# Sheet1.net
KiCad netlist of a schematic drawn in Altium Designer
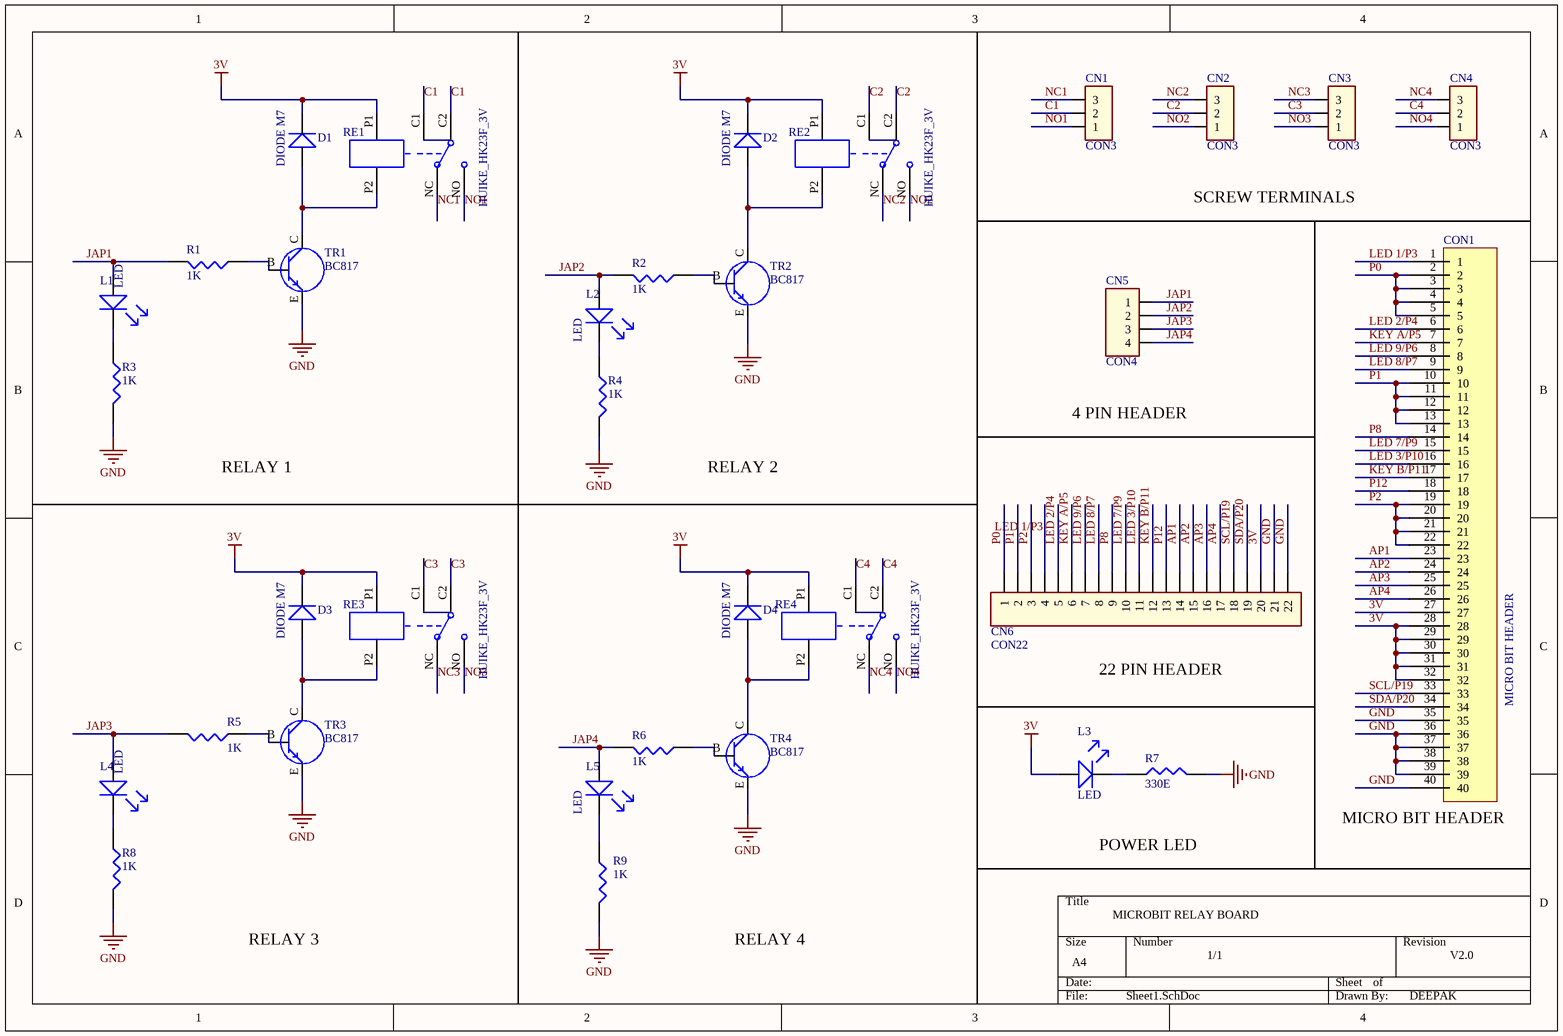
[diagram p0: Sheet1.SchDoc]

(export (version "E")
  (design (tool "Eeschema 10.0.6"))
  (components
    (comp (ref "CN1") (value "CON3") (footprint "CON3_3.5") (libsource (lib "dxp_pasl_lib") (part "CON3")))
    (comp (ref "CN2") (value "CON3") (footprint "CON3_3.5") (libsource (lib "dxp_pasl_lib") (part "CON3")))
    (comp (ref "CN3") (value "CON3") (footprint "CON3_3.5") (libsource (lib "dxp_pasl_lib") (part "CON3")))
    (comp (ref "CN4") (value "CON3") (footprint "CON3_3.5") (libsource (lib "dxp_pasl_lib") (part "CON3")))
    (comp (ref "CN5") (value "CON4") (footprint "CON4_BJ") (libsource (lib "dxp_pasl_lib") (part "CON4")))
    (comp (ref "CN6")
      (value "CON22")
      (footprint "CON22  berg")
      (libsource (lib "dxp_pasl_lib") (part "CON22"))
    )
    (comp (ref "CON1")
      (value "MICRO BIT HEADER")
      (footprint "MICROBIT HEADER STRAIGHT")
      (libsource (lib "dxp_pasl_lib") (part "MICRO BIT HEADER 40 PIN"))
    )
    (comp (ref "D1")
      (value "DIODE M7")
      (footprint "M7 SMO_DO-214AC")
      (libsource (lib "dxp_pasl_lib") (part "DIODE"))
    )
    (comp (ref "D2")
      (value "DIODE M7")
      (footprint "M7 SMO_DO-214AC")
      (libsource (lib "dxp_pasl_lib") (part "DIODE"))
    )
    (comp (ref "D3")
      (value "DIODE M7")
      (footprint "M7 SMO_DO-214AC")
      (libsource (lib "dxp_pasl_lib") (part "DIODE"))
    )
    (comp (ref "D4")
      (value "DIODE M7")
      (footprint "M7 SMO_DO-214AC")
      (libsource (lib "dxp_pasl_lib") (part "DIODE"))
    )
    (comp (ref "L1") (value "LED") (footprint "0805 _LED") (libsource (lib "dxp_pasl_lib") (part "LED")))
    (comp (ref "L2") (value "LED") (footprint "0805 _LED") (libsource (lib "dxp_pasl_lib") (part "LED")))
    (comp (ref "L3") (value "LED") (footprint "0805 _LED") (libsource (lib "dxp_pasl_lib") (part "LED")))
    (comp (ref "L4") (value "LED") (footprint "0805 _LED") (libsource (lib "dxp_pasl_lib") (part "LED")))
    (comp (ref "L5") (value "LED") (footprint "0805 _LED") (libsource (lib "dxp_pasl_lib") (part "LED")))
    (comp (ref "R1") (value "1K") (footprint "0603") (libsource (lib "dxp_pasl_lib") (part "RES")))
    (comp (ref "R2") (value "1K") (footprint "0603") (libsource (lib "dxp_pasl_lib") (part "RES")))
    (comp (ref "R3") (value "1K") (footprint "0603") (libsource (lib "dxp_pasl_lib") (part "RES")))
    (comp (ref "R4") (value "1K") (footprint "0603") (libsource (lib "dxp_pasl_lib") (part "RES")))
    (comp (ref "R5") (value "1K") (footprint "0603") (libsource (lib "dxp_pasl_lib") (part "RES")))
    (comp (ref "R6") (value "1K") (footprint "0603") (libsource (lib "dxp_pasl_lib") (part "RES")))
    (comp (ref "R7") (value "330E") (footprint "0603") (libsource (lib "dxp_pasl_lib") (part "RES")))
    (comp (ref "R8") (value "1K") (footprint "0603") (libsource (lib "dxp_pasl_lib") (part "RES")))
    (comp (ref "R9") (value "1K") (footprint "0603") (libsource (lib "dxp_pasl_lib") (part "RES")))
    (comp (ref "RE1")
      (value "HUIKE_HK23F_3V")
      (footprint "HK23F_RELAY")
      (libsource (lib "dxp_pasl_lib") (part "HUIKE_HK23F_3V"))
    )
    (comp (ref "RE2")
      (value "HUIKE_HK23F_3V")
      (footprint "HK23F_RELAY")
      (libsource (lib "dxp_pasl_lib") (part "HUIKE_HK23F_3V"))
    )
    (comp (ref "RE3")
      (value "HUIKE_HK23F_3V")
      (footprint "HK23F_RELAY")
      (libsource (lib "dxp_pasl_lib") (part "HUIKE_HK23F_3V"))
    )
    (comp (ref "RE4")
      (value "HUIKE_HK23F_3V")
      (footprint "HK23F_RELAY")
      (libsource (lib "dxp_pasl_lib") (part "HUIKE_HK23F_3V"))
    )
    (comp (ref "TR1")
      (value "BC817")
      (footprint "547_SOT23")
      (libsource (lib "dxp_pasl_lib") (part "TRANSISTER_NPN"))
    )
    (comp (ref "TR2")
      (value "BC817")
      (footprint "547_SOT23")
      (libsource (lib "dxp_pasl_lib") (part "TRANSISTER_NPN"))
    )
    (comp (ref "TR3")
      (value "BC817")
      (footprint "547_SOT23")
      (libsource (lib "dxp_pasl_lib") (part "TRANSISTER_NPN"))
    )
    (comp (ref "TR4")
      (value "BC817")
      (footprint "547_SOT23")
      (libsource (lib "dxp_pasl_lib") (part "TRANSISTER_NPN"))
    )
  )
  (nets
    (net (code "1") (name "/AP1") (class "Default")
      (node (ref "CN6") (pin "14") (pinfunction "14_14") (pintype "passive"))
      (node (ref "CON1") (pin "23") (pinfunction "23_23") (pintype "passive"))
    )
    (net (code "2") (name "/AP2") (class "Default")
      (node (ref "CN6") (pin "15") (pinfunction "15_15") (pintype "passive"))
      (node (ref "CON1") (pin "24") (pinfunction "24_24") (pintype "passive"))
    )
    (net (code "3") (name "/AP3") (class "Default")
      (node (ref "CN6") (pin "16") (pinfunction "16_16") (pintype "passive"))
      (node (ref "CON1") (pin "25") (pinfunction "25_25") (pintype "passive"))
    )
    (net (code "4") (name "/AP4") (class "Default")
      (node (ref "CN6") (pin "17") (pinfunction "17_17") (pintype "passive"))
      (node (ref "CON1") (pin "26") (pinfunction "26_26") (pintype "passive"))
    )
    (net (code "5") (name "/C1") (class "Default")
      (node (ref "CN1") (pin "2") (pinfunction "2_2") (pintype "passive"))
      (node (ref "RE1") (pin "C1") (pinfunction "C1_C1") (pintype "passive"))
      (node (ref "RE1") (pin "C2") (pinfunction "C2_C2") (pintype "passive"))
    )
    (net (code "6") (name "/C2") (class "Default")
      (node (ref "CN2") (pin "2") (pinfunction "2_2") (pintype "passive"))
      (node (ref "RE2") (pin "C1") (pinfunction "C1_C1") (pintype "passive"))
      (node (ref "RE2") (pin "C2") (pinfunction "C2_C2") (pintype "passive"))
    )
    (net (code "7") (name "/C3") (class "Default")
      (node (ref "CN3") (pin "2") (pinfunction "2_2") (pintype "passive"))
      (node (ref "RE3") (pin "C1") (pinfunction "C1_C1") (pintype "passive"))
      (node (ref "RE3") (pin "C2") (pinfunction "C2_C2") (pintype "passive"))
    )
    (net (code "8") (name "/C4") (class "Default")
      (node (ref "CN4") (pin "2") (pinfunction "2_2") (pintype "passive"))
      (node (ref "RE4") (pin "C1") (pinfunction "C1_C1") (pintype "passive"))
      (node (ref "RE4") (pin "C2") (pinfunction "C2_C2") (pintype "passive"))
    )
    (net (code "9") (name "/JAP1") (class "Default")
      (node (ref "CN5") (pin "1") (pinfunction "1_1") (pintype "passive"))
      (node (ref "L1") (pin "A") (pinfunction "A_A") (pintype "passive"))
      (node (ref "R1") (pin "2") (pinfunction "2_2") (pintype "passive"))
    )
    (net (code "10") (name "/JAP2") (class "Default")
      (node (ref "CN5") (pin "2") (pinfunction "2_2") (pintype "passive"))
      (node (ref "L2") (pin "A") (pinfunction "A_A") (pintype "passive"))
      (node (ref "R2") (pin "2") (pinfunction "2_2") (pintype "passive"))
    )
    (net (code "11") (name "/JAP3") (class "Default")
      (node (ref "CN5") (pin "3") (pinfunction "3_3") (pintype "passive"))
      (node (ref "L4") (pin "A") (pinfunction "A_A") (pintype "passive"))
      (node (ref "R5") (pin "2") (pinfunction "2_2") (pintype "passive"))
    )
    (net (code "12") (name "/JAP4") (class "Default")
      (node (ref "CN5") (pin "4") (pinfunction "4_4") (pintype "passive"))
      (node (ref "L5") (pin "A") (pinfunction "A_A") (pintype "passive"))
      (node (ref "R6") (pin "2") (pinfunction "2_2") (pintype "passive"))
    )
    (net (code "13") (name "/KEY A{slash}P5") (class "Default")
      (node (ref "CN6") (pin "6") (pinfunction "6_6") (pintype "passive"))
      (node (ref "CON1") (pin "7") (pinfunction "7_7") (pintype "passive"))
    )
    (net (code "14") (name "/KEY B{slash}P11") (class "Default")
      (node (ref "CN6") (pin "12") (pinfunction "12_12") (pintype "passive"))
      (node (ref "CON1") (pin "17") (pinfunction "17_17") (pintype "passive"))
    )
    (net (code "15") (name "/LED 1{slash}P3") (class "Default")
      (node (ref "CN6") (pin "4") (pinfunction "4_4") (pintype "passive"))
      (node (ref "CON1") (pin "1") (pinfunction "1_1") (pintype "passive"))
    )
    (net (code "16") (name "/LED 2{slash}P4") (class "Default")
      (node (ref "CN6") (pin "5") (pinfunction "5_5") (pintype "passive"))
      (node (ref "CON1") (pin "6") (pinfunction "6_6") (pintype "passive"))
    )
    (net (code "17") (name "/LED 3{slash}P10") (class "Default")
      (node (ref "CN6") (pin "11") (pinfunction "11_11") (pintype "passive"))
      (node (ref "CON1") (pin "16") (pinfunction "16_16") (pintype "passive"))
    )
    (net (code "18") (name "/LED 7{slash}P9") (class "Default")
      (node (ref "CN6") (pin "10") (pinfunction "10_10") (pintype "passive"))
      (node (ref "CON1") (pin "15") (pinfunction "15_15") (pintype "passive"))
    )
    (net (code "19") (name "/LED 8{slash}P7") (class "Default")
      (node (ref "CN6") (pin "8") (pinfunction "8_8") (pintype "passive"))
      (node (ref "CON1") (pin "9") (pinfunction "9_9") (pintype "passive"))
    )
    (net (code "20") (name "/LED 9{slash}P6") (class "Default")
      (node (ref "CN6") (pin "7") (pinfunction "7_7") (pintype "passive"))
      (node (ref "CON1") (pin "8") (pinfunction "8_8") (pintype "passive"))
    )
    (net (code "21") (name "/NC1") (class "Default")
      (node (ref "CN1") (pin "3") (pinfunction "3_3") (pintype "passive"))
      (node (ref "RE1") (pin "NC") (pinfunction "NC_NC") (pintype "passive"))
    )
    (net (code "22") (name "/NC2") (class "Default")
      (node (ref "CN2") (pin "3") (pinfunction "3_3") (pintype "passive"))
      (node (ref "RE2") (pin "NC") (pinfunction "NC_NC") (pintype "passive"))
    )
    (net (code "23") (name "/NC3") (class "Default")
      (node (ref "CN3") (pin "3") (pinfunction "3_3") (pintype "passive"))
      (node (ref "RE3") (pin "NC") (pinfunction "NC_NC") (pintype "passive"))
    )
    (net (code "24") (name "/NC4") (class "Default")
      (node (ref "CN4") (pin "3") (pinfunction "3_3") (pintype "passive"))
      (node (ref "RE4") (pin "NC") (pinfunction "NC_NC") (pintype "passive"))
    )
    (net (code "25") (name "/NO1") (class "Default")
      (node (ref "CN1") (pin "1") (pinfunction "1_1") (pintype "passive"))
      (node (ref "RE1") (pin "NO") (pinfunction "NO_NO") (pintype "passive"))
    )
    (net (code "26") (name "/NO2") (class "Default")
      (node (ref "CN2") (pin "1") (pinfunction "1_1") (pintype "passive"))
      (node (ref "RE2") (pin "NO") (pinfunction "NO_NO") (pintype "passive"))
    )
    (net (code "27") (name "/NO3") (class "Default")
      (node (ref "CN3") (pin "1") (pinfunction "1_1") (pintype "passive"))
      (node (ref "RE3") (pin "NO") (pinfunction "NO_NO") (pintype "passive"))
    )
    (net (code "28") (name "/NO4") (class "Default")
      (node (ref "CN4") (pin "1") (pinfunction "1_1") (pintype "passive"))
      (node (ref "RE4") (pin "NO") (pinfunction "NO_NO") (pintype "passive"))
    )
    (net (code "29") (name "/P0") (class "Default")
      (node (ref "CN6") (pin "1") (pinfunction "1_1") (pintype "passive"))
      (node (ref "CON1") (pin "2") (pinfunction "2_2") (pintype "passive"))
      (node (ref "CON1") (pin "3") (pinfunction "3_3") (pintype "passive"))
      (node (ref "CON1") (pin "4") (pinfunction "4_4") (pintype "passive"))
      (node (ref "CON1") (pin "5") (pinfunction "5_5") (pintype "passive"))
    )
    (net (code "30") (name "/P1") (class "Default")
      (node (ref "CN6") (pin "2") (pinfunction "2_2") (pintype "passive"))
      (node (ref "CON1") (pin "10") (pinfunction "10_10") (pintype "passive"))
      (node (ref "CON1") (pin "11") (pinfunction "11_11") (pintype "passive"))
      (node (ref "CON1") (pin "12") (pinfunction "12_12") (pintype "passive"))
      (node (ref "CON1") (pin "13") (pinfunction "13_13") (pintype "passive"))
    )
    (net (code "31") (name "/P2") (class "Default")
      (node (ref "CN6") (pin "3") (pinfunction "3_3") (pintype "passive"))
      (node (ref "CON1") (pin "19") (pinfunction "19_19") (pintype "passive"))
      (node (ref "CON1") (pin "20") (pinfunction "20_20") (pintype "passive"))
      (node (ref "CON1") (pin "21") (pinfunction "21_21") (pintype "passive"))
      (node (ref "CON1") (pin "22") (pinfunction "22_22") (pintype "passive"))
    )
    (net (code "32") (name "/P8") (class "Default")
      (node (ref "CN6") (pin "9") (pinfunction "9_9") (pintype "passive"))
      (node (ref "CON1") (pin "14") (pinfunction "14_14") (pintype "passive"))
    )
    (net (code "33") (name "/P12") (class "Default")
      (node (ref "CN6") (pin "13") (pinfunction "13_13") (pintype "passive"))
      (node (ref "CON1") (pin "18") (pinfunction "18_18") (pintype "passive"))
    )
    (net (code "34") (name "/SCL{slash}P19") (class "Default")
      (node (ref "CN6") (pin "18") (pinfunction "18_18") (pintype "passive"))
      (node (ref "CON1") (pin "33") (pinfunction "33_33") (pintype "passive"))
    )
    (net (code "35") (name "/SDA{slash}P20") (class "Default")
      (node (ref "CN6") (pin "19") (pinfunction "19_19") (pintype "passive"))
      (node (ref "CON1") (pin "34") (pinfunction "34_34") (pintype "passive"))
    )
    (net (code "36") (name "3V") (class "Default")
      (node (ref "CN6") (pin "20") (pinfunction "20_20") (pintype "passive"))
      (node (ref "CON1") (pin "27") (pinfunction "27_27") (pintype "passive"))
      (node (ref "CON1") (pin "28") (pinfunction "28_28") (pintype "passive"))
      (node (ref "CON1") (pin "29") (pinfunction "29_29") (pintype "passive"))
      (node (ref "CON1") (pin "30") (pinfunction "30_30") (pintype "passive"))
      (node (ref "CON1") (pin "31") (pinfunction "31_31") (pintype "passive"))
      (node (ref "CON1") (pin "32") (pinfunction "32_32") (pintype "passive"))
      (node (ref "D1") (pin "K") (pinfunction "K_K") (pintype "passive"))
      (node (ref "D2") (pin "K") (pinfunction "K_K") (pintype "passive"))
      (node (ref "D3") (pin "K") (pinfunction "K_K") (pintype "passive"))
      (node (ref "D4") (pin "K") (pinfunction "K_K") (pintype "passive"))
      (node (ref "L3") (pin "A") (pinfunction "A_A") (pintype "passive"))
      (node (ref "RE1") (pin "P1") (pinfunction "P1_P1") (pintype "passive"))
      (node (ref "RE2") (pin "P1") (pinfunction "P1_P1") (pintype "passive"))
      (node (ref "RE3") (pin "P1") (pinfunction "P1_P1") (pintype "passive"))
      (node (ref "RE4") (pin "P1") (pinfunction "P1_P1") (pintype "passive"))
    )
    (net (code "37") (name "GND") (class "Default")
      (node (ref "CN6") (pin "21") (pinfunction "21_21") (pintype "passive"))
      (node (ref "CN6") (pin "22") (pinfunction "22_22") (pintype "passive"))
      (node (ref "CON1") (pin "35") (pinfunction "35_35") (pintype "passive"))
      (node (ref "CON1") (pin "36") (pinfunction "36_36") (pintype "passive"))
      (node (ref "CON1") (pin "37") (pinfunction "37_37") (pintype "passive"))
      (node (ref "CON1") (pin "38") (pinfunction "38_38") (pintype "passive"))
      (node (ref "CON1") (pin "39") (pinfunction "39_39") (pintype "passive"))
      (node (ref "CON1") (pin "40") (pinfunction "40_40") (pintype "passive"))
      (node (ref "R3") (pin "2") (pinfunction "2_2") (pintype "passive"))
      (node (ref "R4") (pin "2") (pinfunction "2_2") (pintype "passive"))
      (node (ref "R7") (pin "2") (pinfunction "2_2") (pintype "passive"))
      (node (ref "R8") (pin "2") (pinfunction "2_2") (pintype "passive"))
      (node (ref "R9") (pin "2") (pinfunction "2_2") (pintype "passive"))
      (node (ref "TR1") (pin "E") (pinfunction "E_E") (pintype "passive"))
      (node (ref "TR2") (pin "E") (pinfunction "E_E") (pintype "passive"))
      (node (ref "TR3") (pin "E") (pinfunction "E_E") (pintype "passive"))
      (node (ref "TR4") (pin "E") (pinfunction "E_E") (pintype "passive"))
    )
    (net (code "38") (name "Net-(D1-PadA)") (class "Default")
      (node (ref "D1") (pin "A") (pinfunction "A_A") (pintype "passive"))
      (node (ref "RE1") (pin "P2") (pinfunction "P2_P2") (pintype "passive"))
      (node (ref "TR1") (pin "C") (pinfunction "C_C") (pintype "passive"))
    )
    (net (code "39") (name "Net-(D2-PadA)") (class "Default")
      (node (ref "D2") (pin "A") (pinfunction "A_A") (pintype "passive"))
      (node (ref "RE2") (pin "P2") (pinfunction "P2_P2") (pintype "passive"))
      (node (ref "TR2") (pin "C") (pinfunction "C_C") (pintype "passive"))
    )
    (net (code "40") (name "Net-(D3-PadA)") (class "Default")
      (node (ref "D3") (pin "A") (pinfunction "A_A") (pintype "passive"))
      (node (ref "RE3") (pin "P2") (pinfunction "P2_P2") (pintype "passive"))
      (node (ref "TR3") (pin "C") (pinfunction "C_C") (pintype "passive"))
    )
    (net (code "41") (name "Net-(D4-PadA)") (class "Default")
      (node (ref "D4") (pin "A") (pinfunction "A_A") (pintype "passive"))
      (node (ref "RE4") (pin "P2") (pinfunction "P2_P2") (pintype "passive"))
      (node (ref "TR4") (pin "C") (pinfunction "C_C") (pintype "passive"))
    )
    (net (code "42") (name "Net-(L1-PadK)") (class "Default")
      (node (ref "L1") (pin "K") (pinfunction "K_K") (pintype "passive"))
      (node (ref "R3") (pin "1") (pinfunction "1_1") (pintype "passive"))
    )
    (net (code "43") (name "Net-(L2-PadK)") (class "Default")
      (node (ref "L2") (pin "K") (pinfunction "K_K") (pintype "passive"))
      (node (ref "R4") (pin "1") (pinfunction "1_1") (pintype "passive"))
    )
    (net (code "44") (name "Net-(L3-PadK)") (class "Default")
      (node (ref "L3") (pin "K") (pinfunction "K_K") (pintype "passive"))
      (node (ref "R7") (pin "1") (pinfunction "1_1") (pintype "passive"))
    )
    (net (code "45") (name "Net-(L4-PadK)") (class "Default")
      (node (ref "L4") (pin "K") (pinfunction "K_K") (pintype "passive"))
      (node (ref "R8") (pin "1") (pinfunction "1_1") (pintype "passive"))
    )
    (net (code "46") (name "Net-(L5-PadK)") (class "Default")
      (node (ref "L5") (pin "K") (pinfunction "K_K") (pintype "passive"))
      (node (ref "R9") (pin "1") (pinfunction "1_1") (pintype "passive"))
    )
    (net (code "47") (name "Net-(R1-Pad1)") (class "Default")
      (node (ref "R1") (pin "1") (pinfunction "1_1") (pintype "passive"))
      (node (ref "TR1") (pin "B") (pinfunction "B_B") (pintype "passive"))
    )
    (net (code "48") (name "Net-(R2-Pad1)") (class "Default")
      (node (ref "R2") (pin "1") (pinfunction "1_1") (pintype "passive"))
      (node (ref "TR2") (pin "B") (pinfunction "B_B") (pintype "passive"))
    )
    (net (code "49") (name "Net-(R5-Pad1)") (class "Default")
      (node (ref "R5") (pin "1") (pinfunction "1_1") (pintype "passive"))
      (node (ref "TR3") (pin "B") (pinfunction "B_B") (pintype "passive"))
    )
    (net (code "50") (name "Net-(R6-Pad1)") (class "Default")
      (node (ref "R6") (pin "1") (pinfunction "1_1") (pintype "passive"))
      (node (ref "TR4") (pin "B") (pinfunction "B_B") (pintype "passive"))
    )
  )
)
